# Power_MOSFETS.net
KiCad netlist of a schematic drawn in Altium Designer
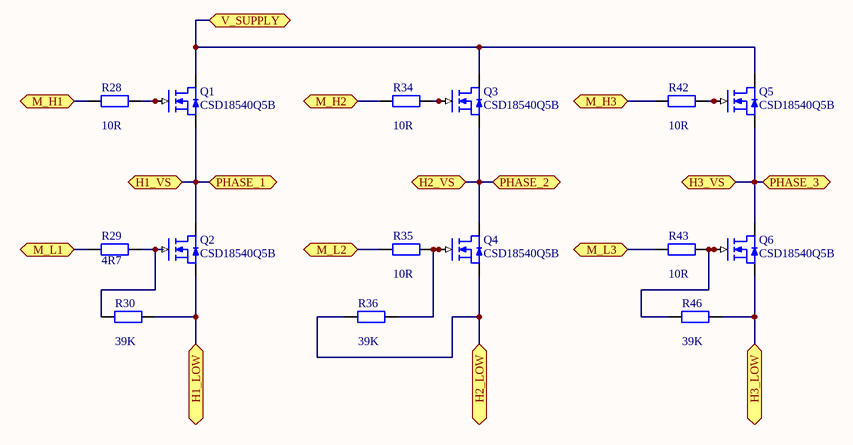
[diagram p0: Power MOSFETS.SchDoc]

(export (version "E")
  (design (tool "Eeschema 10.0.6"))
  (components
    (comp (ref "Q1")
      (value "CSD18540Q5B")
      (footprint "SON5X6")
      (libsource (lib "TAOXUN") (part "CSD18540Q5B"))
    )
    (comp (ref "Q2")
      (value "CSD18540Q5B")
      (footprint "SON5X6")
      (libsource (lib "TAOXUN") (part "CSD18540Q5B"))
    )
    (comp (ref "Q3")
      (value "CSD18540Q5B")
      (footprint "SON5X6")
      (libsource (lib "TAOXUN") (part "CSD18540Q5B"))
    )
    (comp (ref "Q4")
      (value "CSD18540Q5B")
      (footprint "SON5X6")
      (libsource (lib "TAOXUN") (part "CSD18540Q5B"))
    )
    (comp (ref "Q5")
      (value "CSD18540Q5B")
      (footprint "SON5X6")
      (libsource (lib "TAOXUN") (part "CSD18540Q5B"))
    )
    (comp (ref "Q6")
      (value "CSD18540Q5B")
      (footprint "SON5X6")
      (libsource (lib "TAOXUN") (part "CSD18540Q5B"))
    )
    (comp (ref "R28")
      (value "10R")
      (footprint "0603-2")
      (description "贴片电阻")
      (fields (field (name "PUBLISHER") "Altium Limited"))
      (libsource (lib "TAOXUN") (part "Res1"))
    )
    (comp (ref "R29")
      (value "4R7")
      (footprint "0603-2")
      (description "贴片电阻")
      (fields (field (name "Comment") "10R") (field (name "PUBLISHER") "Altium Limited"))
      (libsource (lib "TAOXUN") (part "Res1"))
    )
    (comp (ref "R30")
      (value "39K")
      (footprint "0603-2")
      (description "贴片电阻")
      (fields (field (name "PUBLISHER") "Altium Limited"))
      (libsource (lib "TAOXUN") (part "Res1"))
    )
    (comp (ref "R34")
      (value "10R")
      (footprint "0603-2")
      (description "贴片电阻")
      (fields (field (name "PUBLISHER") "Altium Limited"))
      (libsource (lib "TAOXUN") (part "Res1"))
    )
    (comp (ref "R35")
      (value "10R")
      (footprint "0603-2")
      (description "贴片电阻")
      (fields (field (name "PUBLISHER") "Altium Limited"))
      (libsource (lib "TAOXUN") (part "Res1"))
    )
    (comp (ref "R36")
      (value "39K")
      (footprint "0603-2")
      (description "贴片电阻")
      (fields (field (name "PUBLISHER") "Altium Limited"))
      (libsource (lib "TAOXUN") (part "Res1"))
    )
    (comp (ref "R42")
      (value "10R")
      (footprint "0603-2")
      (description "贴片电阻")
      (fields (field (name "PUBLISHER") "Altium Limited"))
      (libsource (lib "TAOXUN") (part "Res1"))
    )
    (comp (ref "R43")
      (value "10R")
      (footprint "0603-2")
      (description "贴片电阻")
      (fields (field (name "PUBLISHER") "Altium Limited"))
      (libsource (lib "TAOXUN") (part "Res1"))
    )
    (comp (ref "R46")
      (value "39K")
      (footprint "0603-2")
      (description "贴片电阻")
      (fields (field (name "PUBLISHER") "Altium Limited"))
      (libsource (lib "TAOXUN") (part "Res1"))
    )
  )
  (nets
    (net (code "1") (name "/H1_LOW") (class "Default")
      (node (ref "Q2") (pin "1") (pinfunction "S_1") (pintype "power_in"))
      (node (ref "R30") (pin "2") (pinfunction "2_2") (pintype "passive"))
    )
    (net (code "2") (name "/H1_VS") (class "Default")
      (node (ref "Q1") (pin "1") (pinfunction "S_1") (pintype "power_in"))
      (node (ref "Q2") (pin "8") (pinfunction "D_8") (pintype "power_in"))
    )
    (net (code "3") (name "/H2_LOW") (class "Default")
      (node (ref "Q4") (pin "1") (pinfunction "S_1") (pintype "power_in"))
      (node (ref "R36") (pin "1") (pinfunction "1_1") (pintype "passive"))
    )
    (net (code "4") (name "/H2_VS") (class "Default")
      (node (ref "Q3") (pin "1") (pinfunction "S_1") (pintype "power_in"))
      (node (ref "Q4") (pin "8") (pinfunction "D_8") (pintype "power_in"))
    )
    (net (code "5") (name "/H3_LOW") (class "Default")
      (node (ref "Q6") (pin "1") (pinfunction "S_1") (pintype "power_in"))
      (node (ref "R46") (pin "2") (pinfunction "2_2") (pintype "passive"))
    )
    (net (code "6") (name "/H3_VS") (class "Default")
      (node (ref "Q5") (pin "1") (pinfunction "S_1") (pintype "power_in"))
      (node (ref "Q6") (pin "8") (pinfunction "D_8") (pintype "power_in"))
    )
    (net (code "7") (name "/M_H1") (class "Default")
      (node (ref "R28") (pin "1") (pinfunction "1_1") (pintype "passive"))
    )
    (net (code "8") (name "/M_H2") (class "Default")
      (node (ref "R34") (pin "1") (pinfunction "1_1") (pintype "passive"))
    )
    (net (code "9") (name "/M_H3") (class "Default")
      (node (ref "R42") (pin "1") (pinfunction "1_1") (pintype "passive"))
    )
    (net (code "10") (name "/M_L1") (class "Default")
      (node (ref "R29") (pin "1") (pinfunction "1_1") (pintype "passive"))
    )
    (net (code "11") (name "/M_L2") (class "Default")
      (node (ref "R35") (pin "1") (pinfunction "1_1") (pintype "passive"))
    )
    (net (code "12") (name "/M_L3") (class "Default")
      (node (ref "R43") (pin "1") (pinfunction "1_1") (pintype "passive"))
    )
    (net (code "13") (name "/V_SUPPLY") (class "Default")
      (node (ref "Q1") (pin "8") (pinfunction "D_8") (pintype "power_in"))
      (node (ref "Q3") (pin "8") (pinfunction "D_8") (pintype "power_in"))
      (node (ref "Q5") (pin "8") (pinfunction "D_8") (pintype "power_in"))
    )
    (net (code "14") (name "Net-(Q1-G)") (class "Default")
      (node (ref "Q1") (pin "4") (pinfunction "G_4") (pintype "input"))
      (node (ref "R28") (pin "2") (pinfunction "2_2") (pintype "passive"))
    )
    (net (code "15") (name "Net-(Q2-G)") (class "Default")
      (node (ref "Q2") (pin "4") (pinfunction "G_4") (pintype "input"))
      (node (ref "R29") (pin "2") (pinfunction "2_2") (pintype "passive"))
      (node (ref "R30") (pin "1") (pinfunction "1_1") (pintype "passive"))
    )
    (net (code "16") (name "Net-(Q3-G)") (class "Default")
      (node (ref "Q3") (pin "4") (pinfunction "G_4") (pintype "input"))
      (node (ref "R34") (pin "2") (pinfunction "2_2") (pintype "passive"))
    )
    (net (code "17") (name "Net-(Q4-G)") (class "Default")
      (node (ref "Q4") (pin "4") (pinfunction "G_4") (pintype "input"))
      (node (ref "R35") (pin "2") (pinfunction "2_2") (pintype "passive"))
      (node (ref "R36") (pin "2") (pinfunction "2_2") (pintype "passive"))
    )
    (net (code "18") (name "Net-(Q5-G)") (class "Default")
      (node (ref "Q5") (pin "4") (pinfunction "G_4") (pintype "input"))
      (node (ref "R42") (pin "2") (pinfunction "2_2") (pintype "passive"))
    )
    (net (code "19") (name "Net-(Q6-G)") (class "Default")
      (node (ref "Q6") (pin "4") (pinfunction "G_4") (pintype "input"))
      (node (ref "R43") (pin "2") (pinfunction "2_2") (pintype "passive"))
      (node (ref "R46") (pin "1") (pinfunction "1_1") (pintype "passive"))
    )
  )
)
